# RFM69-ESP-03-v1_0.net
KiCad netlist of a schematic drawn in EAGLE
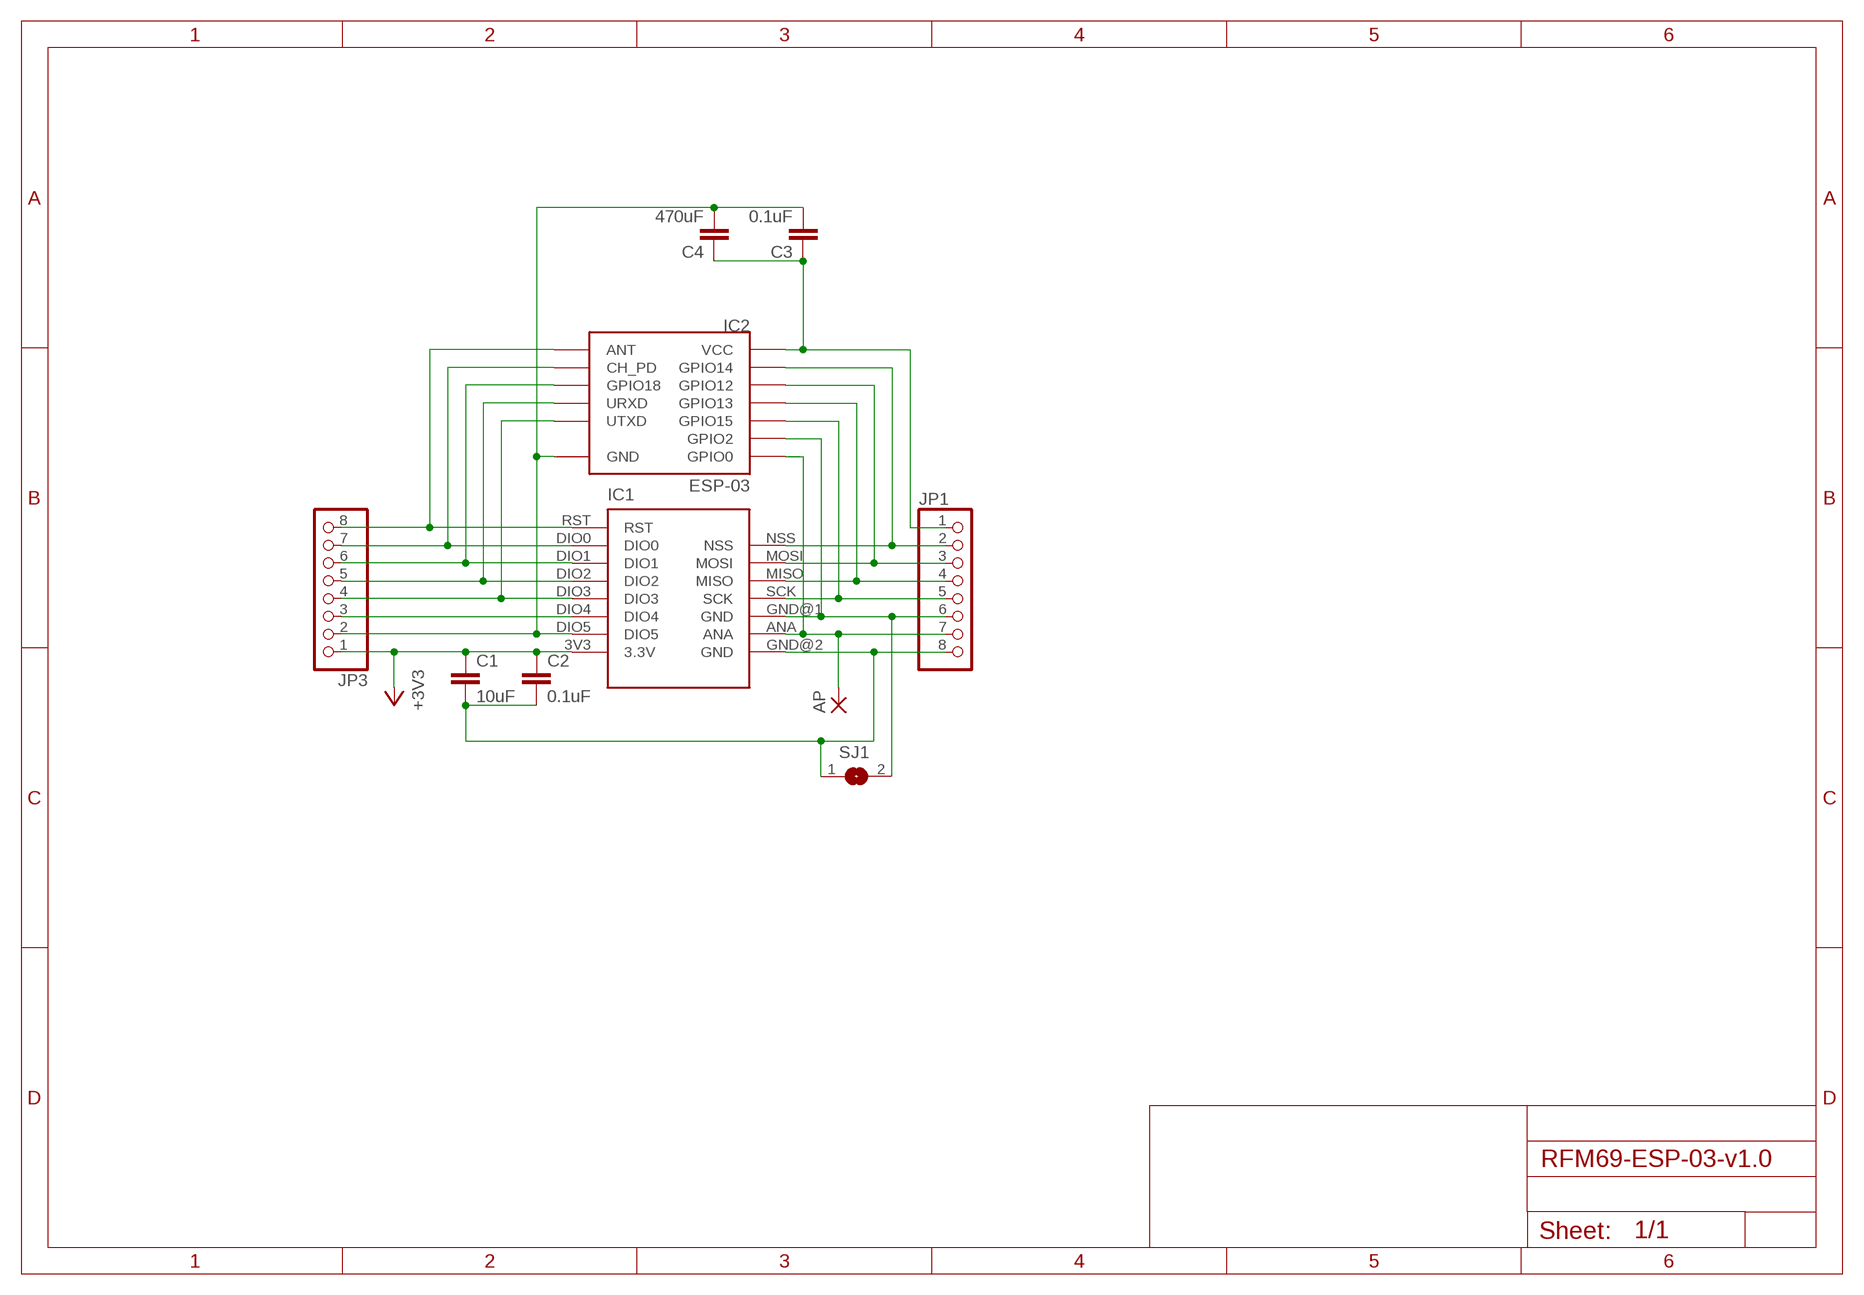
[diagram p0: schematic, sheet 1]

(export (version "E")
  (design (tool "Eeschema 10.0.6"))
  (components
    (comp (ref "AP")
      (value "SMD5")
      (footprint "eagle-import:SMD2,54-5,08")
      (libsource (lib "eagle-import") (part "SMD5"))
    )
    (comp (ref "C1")
      (value "10uF")
      (footprint "eagle-import:C1206")
      (libsource (lib "eagle-import") (part "C-EUC1206"))
    )
    (comp (ref "C2")
      (value "0.1uF")
      (footprint "eagle-import:C1206")
      (libsource (lib "eagle-import") (part "C-EUC1206"))
    )
    (comp (ref "C3")
      (value "0.1uF")
      (footprint "eagle-import:C1206")
      (libsource (lib "eagle-import") (part "C-EUC1206"))
    )
    (comp (ref "C4")
      (value "470uF")
      (footprint "eagle-import:C1206")
      (libsource (lib "eagle-import") (part "C-EUC1206"))
    )
    (comp (ref "IC1")
      (value "RFM69HW")
      (footprint "eagle-import:RFM69")
      (libsource (lib "eagle-import") (part "RFM69HW"))
    )
    (comp (ref "IC2")
      (value "ESP-03")
      (footprint "eagle-import:ESP-03")
      (libsource (lib "eagle-import") (part "ESP-03"))
    )
    (comp (ref "JP1")
      (value "PINHD-1X8")
      (footprint "eagle-import:1X08")
      (libsource (lib "eagle-import") (part "PINHD-1X8"))
    )
    (comp (ref "JP3")
      (value "PINHD-1X8")
      (footprint "eagle-import:1X08")
      (libsource (lib "eagle-import") (part "PINHD-1X8"))
    )
    (comp (ref "SJ1") (value "SJ") (footprint "eagle-import:SJ") (libsource (lib "eagle-import") (part "SJ")))
  )
  (nets
    (net (code "1") (name "+3V3") (class "Default")
      (node (ref "C1") (pin "1") (pinfunction "1_1") (pintype "passive"))
      (node (ref "C2") (pin "1") (pinfunction "1_1") (pintype "passive"))
      (node (ref "IC1") (pin "3V3") (pinfunction "3.3V_3V3") (pintype "power_in"))
      (node (ref "JP3") (pin "1") (pinfunction "1_1") (pintype "passive"))
    )
    (net (code "2") (name "Net-(AP-P)") (class "Default")
      (node (ref "AP") (pin "1") (pinfunction "P_1") (pintype "passive"))
      (node (ref "IC1") (pin "ANA") (pinfunction "ANA_ANA") (pintype "bidirectional"))
      (node (ref "IC2") (pin "GPIO0") (pinfunction "GPIO0_GPIO0") (pintype "bidirectional"))
      (node (ref "JP1") (pin "7") (pinfunction "7_7") (pintype "passive"))
    )
    (net (code "3") (name "Net-(C1-Pad2)") (class "Default")
      (node (ref "C1") (pin "2") (pinfunction "2_2") (pintype "passive"))
      (node (ref "C2") (pin "2") (pinfunction "2_2") (pintype "passive"))
      (node (ref "IC1") (pin "GND@2") (pinfunction "GND_GND@2") (pintype "power_in"))
      (node (ref "JP1") (pin "8") (pinfunction "8_8") (pintype "passive"))
      (node (ref "SJ1") (pin "1") (pinfunction "1_1") (pintype "passive"))
    )
    (net (code "4") (name "Net-(C3-Pad1)") (class "Default")
      (node (ref "C3") (pin "1") (pinfunction "1_1") (pintype "passive"))
      (node (ref "C4") (pin "1") (pinfunction "1_1") (pintype "passive"))
      (node (ref "IC2") (pin "VCC") (pinfunction "VCC_VCC") (pintype "bidirectional"))
      (node (ref "JP1") (pin "1") (pinfunction "1_1") (pintype "passive"))
    )
    (net (code "5") (name "Net-(C3-Pad2)") (class "Default")
      (node (ref "C3") (pin "2") (pinfunction "2_2") (pintype "passive"))
      (node (ref "C4") (pin "2") (pinfunction "2_2") (pintype "passive"))
      (node (ref "IC1") (pin "DIO5") (pinfunction "DIO5_DIO5") (pintype "bidirectional"))
      (node (ref "IC2") (pin "GND") (pinfunction "GND_GND") (pintype "bidirectional"))
      (node (ref "JP3") (pin "2") (pinfunction "2_2") (pintype "passive"))
    )
    (net (code "6") (name "Net-(IC1-GND-PadGND@1)") (class "Default")
      (node (ref "IC1") (pin "GND@1") (pinfunction "GND_GND@1") (pintype "power_in"))
      (node (ref "IC2") (pin "GPIO2") (pinfunction "GPIO2_GPIO2") (pintype "bidirectional"))
      (node (ref "JP1") (pin "6") (pinfunction "6_6") (pintype "passive"))
      (node (ref "SJ1") (pin "2") (pinfunction "2_2") (pintype "passive"))
    )
    (net (code "7") (name "Net-(IC1-PadDIO0)") (class "Default")
      (node (ref "IC1") (pin "DIO0") (pinfunction "DIO0_DIO0") (pintype "bidirectional"))
      (node (ref "IC2") (pin "CH_PD") (pinfunction "CH_PD_CH_PD") (pintype "bidirectional"))
      (node (ref "JP3") (pin "7") (pinfunction "7_7") (pintype "passive"))
    )
    (net (code "8") (name "Net-(IC1-PadDIO1)") (class "Default")
      (node (ref "IC1") (pin "DIO1") (pinfunction "DIO1_DIO1") (pintype "bidirectional"))
      (node (ref "IC2") (pin "GPIO18") (pinfunction "GPIO18_GPIO18") (pintype "bidirectional"))
      (node (ref "JP3") (pin "6") (pinfunction "6_6") (pintype "passive"))
    )
    (net (code "9") (name "Net-(IC1-PadDIO2)") (class "Default")
      (node (ref "IC1") (pin "DIO2") (pinfunction "DIO2_DIO2") (pintype "bidirectional"))
      (node (ref "IC2") (pin "URXD") (pinfunction "URXD_URXD") (pintype "bidirectional"))
      (node (ref "JP3") (pin "5") (pinfunction "5_5") (pintype "passive"))
    )
    (net (code "10") (name "Net-(IC1-PadDIO3)") (class "Default")
      (node (ref "IC1") (pin "DIO3") (pinfunction "DIO3_DIO3") (pintype "bidirectional"))
      (node (ref "IC2") (pin "UTXD") (pinfunction "UTXD_UTXD") (pintype "bidirectional"))
      (node (ref "JP3") (pin "4") (pinfunction "4_4") (pintype "passive"))
    )
    (net (code "11") (name "Net-(IC1-PadDIO4)") (class "Default")
      (node (ref "IC1") (pin "DIO4") (pinfunction "DIO4_DIO4") (pintype "bidirectional"))
      (node (ref "JP3") (pin "3") (pinfunction "3_3") (pintype "passive"))
    )
    (net (code "12") (name "Net-(IC1-PadMISO)") (class "Default")
      (node (ref "IC1") (pin "MISO") (pinfunction "MISO_MISO") (pintype "bidirectional"))
      (node (ref "IC2") (pin "GPIO13") (pinfunction "GPIO13_GPIO13") (pintype "bidirectional"))
      (node (ref "JP1") (pin "4") (pinfunction "4_4") (pintype "passive"))
    )
    (net (code "13") (name "Net-(IC1-PadMOSI)") (class "Default")
      (node (ref "IC1") (pin "MOSI") (pinfunction "MOSI_MOSI") (pintype "bidirectional"))
      (node (ref "IC2") (pin "GPIO12") (pinfunction "GPIO12_GPIO12") (pintype "bidirectional"))
      (node (ref "JP1") (pin "3") (pinfunction "3_3") (pintype "passive"))
    )
    (net (code "14") (name "Net-(IC1-PadNSS)") (class "Default")
      (node (ref "IC1") (pin "NSS") (pinfunction "NSS_NSS") (pintype "bidirectional"))
      (node (ref "IC2") (pin "GPIO14") (pinfunction "GPIO14_GPIO14") (pintype "bidirectional"))
      (node (ref "JP1") (pin "2") (pinfunction "2_2") (pintype "passive"))
    )
    (net (code "15") (name "Net-(IC1-PadRST)") (class "Default")
      (node (ref "IC1") (pin "RST") (pinfunction "RST_RST") (pintype "bidirectional"))
      (node (ref "IC2") (pin "ANT") (pinfunction "ANT_ANT") (pintype "bidirectional"))
      (node (ref "JP3") (pin "8") (pinfunction "8_8") (pintype "passive"))
    )
    (net (code "16") (name "Net-(IC1-PadSCK)") (class "Default")
      (node (ref "IC1") (pin "SCK") (pinfunction "SCK_SCK") (pintype "bidirectional"))
      (node (ref "IC2") (pin "GPIO15") (pinfunction "GPIO15_GPIO15") (pintype "bidirectional"))
      (node (ref "JP1") (pin "5") (pinfunction "5_5") (pintype "passive"))
    )
  )
)
